# MotorSteuerung.net
KiCad netlist of a schematic drawn in EAGLE
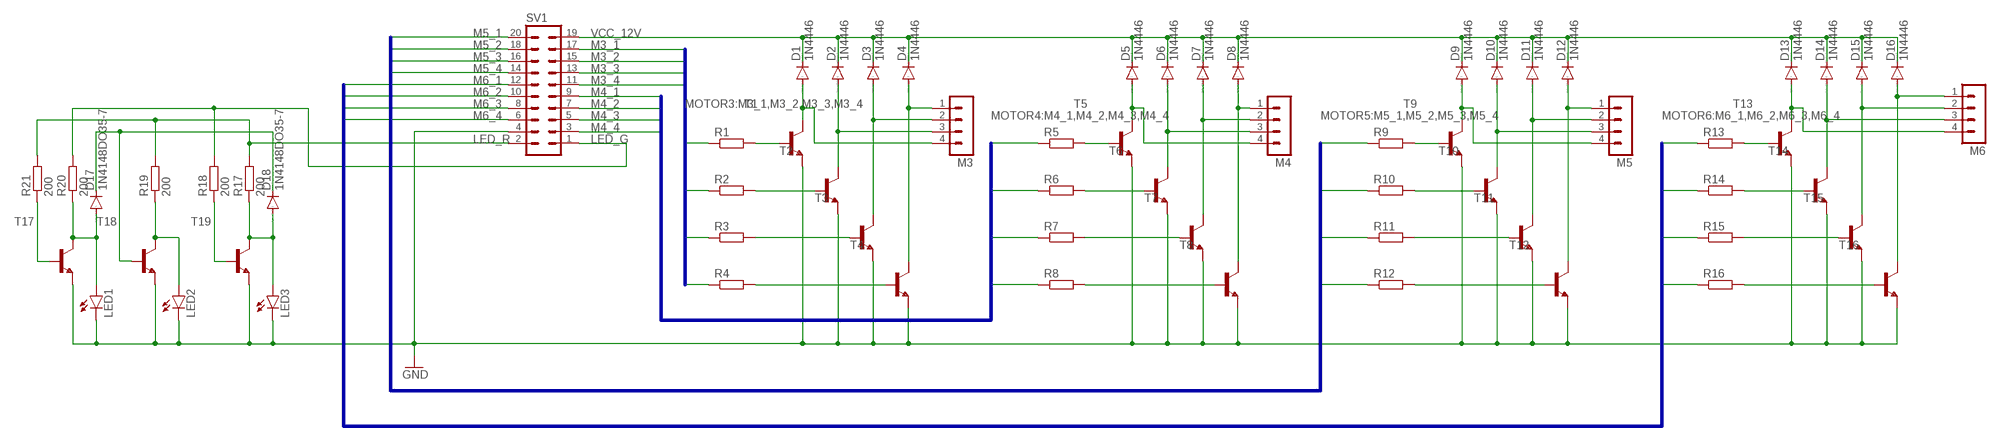
[diagram p0: schematic, sheet 1]

(export (version "E")
  (design (tool "Eeschema 10.0.6"))
  (components
    (comp (ref "D1")
      (value "1N4446")
      (footprint "eagle-import:DO35-10")
      (libsource (lib "eagle-import") (part "1N4446"))
    )
    (comp (ref "D2")
      (value "1N4446")
      (footprint "eagle-import:DO35-10")
      (libsource (lib "eagle-import") (part "1N4446"))
    )
    (comp (ref "D3")
      (value "1N4446")
      (footprint "eagle-import:DO35-10")
      (libsource (lib "eagle-import") (part "1N4446"))
    )
    (comp (ref "D4")
      (value "1N4446")
      (footprint "eagle-import:DO35-10")
      (libsource (lib "eagle-import") (part "1N4446"))
    )
    (comp (ref "D5")
      (value "1N4446")
      (footprint "eagle-import:DO35-10")
      (libsource (lib "eagle-import") (part "1N4446"))
    )
    (comp (ref "D6")
      (value "1N4446")
      (footprint "eagle-import:DO35-10")
      (libsource (lib "eagle-import") (part "1N4446"))
    )
    (comp (ref "D7")
      (value "1N4446")
      (footprint "eagle-import:DO35-10")
      (libsource (lib "eagle-import") (part "1N4446"))
    )
    (comp (ref "D8")
      (value "1N4446")
      (footprint "eagle-import:DO35-10")
      (libsource (lib "eagle-import") (part "1N4446"))
    )
    (comp (ref "D9")
      (value "1N4446")
      (footprint "eagle-import:DO35-10")
      (libsource (lib "eagle-import") (part "1N4446"))
    )
    (comp (ref "D10")
      (value "1N4446")
      (footprint "eagle-import:DO35-10")
      (libsource (lib "eagle-import") (part "1N4446"))
    )
    (comp (ref "D11")
      (value "1N4446")
      (footprint "eagle-import:DO35-10")
      (libsource (lib "eagle-import") (part "1N4446"))
    )
    (comp (ref "D12")
      (value "1N4446")
      (footprint "eagle-import:DO35-10")
      (libsource (lib "eagle-import") (part "1N4446"))
    )
    (comp (ref "D13")
      (value "1N4446")
      (footprint "eagle-import:DO35-10")
      (libsource (lib "eagle-import") (part "1N4446"))
    )
    (comp (ref "D14")
      (value "1N4446")
      (footprint "eagle-import:DO35-10")
      (libsource (lib "eagle-import") (part "1N4446"))
    )
    (comp (ref "D15")
      (value "1N4446")
      (footprint "eagle-import:DO35-10")
      (libsource (lib "eagle-import") (part "1N4446"))
    )
    (comp (ref "D16")
      (value "1N4446")
      (footprint "eagle-import:DO35-10")
      (libsource (lib "eagle-import") (part "1N4446"))
    )
    (comp (ref "D17")
      (value "1N4148DO35-7")
      (footprint "eagle-import:DO35-7")
      (libsource (lib "eagle-import") (part "1N4148DO35-7"))
    )
    (comp (ref "D18")
      (value "1N4148DO35-7")
      (footprint "eagle-import:DO35-7")
      (libsource (lib "eagle-import") (part "1N4148DO35-7"))
    )
    (comp (ref "LED1")
      (value "LED3MM")
      (footprint "eagle-import:LED3MM")
      (libsource (lib "eagle-import") (part "LED3MM"))
    )
    (comp (ref "LED2")
      (value "LED3MM")
      (footprint "eagle-import:LED3MM")
      (libsource (lib "eagle-import") (part "LED3MM"))
    )
    (comp (ref "LED3")
      (value "LED3MM")
      (footprint "eagle-import:LED3MM")
      (libsource (lib "eagle-import") (part "LED3MM"))
    )
    (comp (ref "M3")
      (value "MA04-1")
      (footprint "eagle-import:MA04-1")
      (libsource (lib "eagle-import") (part "MA04-1"))
    )
    (comp (ref "M4")
      (value "MA04-1")
      (footprint "eagle-import:MA04-1")
      (libsource (lib "eagle-import") (part "MA04-1"))
    )
    (comp (ref "M5")
      (value "MA04-1")
      (footprint "eagle-import:MA04-1")
      (libsource (lib "eagle-import") (part "MA04-1"))
    )
    (comp (ref "M6")
      (value "MA04-1")
      (footprint "eagle-import:MA04-1")
      (libsource (lib "eagle-import") (part "MA04-1"))
    )
    (comp (ref "R1")
      (value "R-EU_0207/10")
      (footprint "eagle-import:0207_10")
      (libsource (lib "eagle-import") (part "R-EU_0207/10"))
    )
    (comp (ref "R2")
      (value "R-EU_0207/10")
      (footprint "eagle-import:0207_10")
      (libsource (lib "eagle-import") (part "R-EU_0207/10"))
    )
    (comp (ref "R3")
      (value "R-EU_0207/10")
      (footprint "eagle-import:0207_10")
      (libsource (lib "eagle-import") (part "R-EU_0207/10"))
    )
    (comp (ref "R4")
      (value "R-EU_0207/10")
      (footprint "eagle-import:0207_10")
      (libsource (lib "eagle-import") (part "R-EU_0207/10"))
    )
    (comp (ref "R5")
      (value "R-EU_0207/10")
      (footprint "eagle-import:0207_10")
      (libsource (lib "eagle-import") (part "R-EU_0207/10"))
    )
    (comp (ref "R6")
      (value "R-EU_0207/10")
      (footprint "eagle-import:0207_10")
      (libsource (lib "eagle-import") (part "R-EU_0207/10"))
    )
    (comp (ref "R7")
      (value "R-EU_0207/10")
      (footprint "eagle-import:0207_10")
      (libsource (lib "eagle-import") (part "R-EU_0207/10"))
    )
    (comp (ref "R8")
      (value "R-EU_0207/10")
      (footprint "eagle-import:0207_10")
      (libsource (lib "eagle-import") (part "R-EU_0207/10"))
    )
    (comp (ref "R9")
      (value "R-EU_0207/10")
      (footprint "eagle-import:0207_10")
      (libsource (lib "eagle-import") (part "R-EU_0207/10"))
    )
    (comp (ref "R10")
      (value "R-EU_0207/10")
      (footprint "eagle-import:0207_10")
      (libsource (lib "eagle-import") (part "R-EU_0207/10"))
    )
    (comp (ref "R11")
      (value "R-EU_0207/10")
      (footprint "eagle-import:0207_10")
      (libsource (lib "eagle-import") (part "R-EU_0207/10"))
    )
    (comp (ref "R12")
      (value "R-EU_0207/10")
      (footprint "eagle-import:0207_10")
      (libsource (lib "eagle-import") (part "R-EU_0207/10"))
    )
    (comp (ref "R13")
      (value "R-EU_0207/10")
      (footprint "eagle-import:0207_10")
      (libsource (lib "eagle-import") (part "R-EU_0207/10"))
    )
    (comp (ref "R14")
      (value "R-EU_0207/10")
      (footprint "eagle-import:0207_10")
      (libsource (lib "eagle-import") (part "R-EU_0207/10"))
    )
    (comp (ref "R15")
      (value "R-EU_0207/10")
      (footprint "eagle-import:0207_10")
      (libsource (lib "eagle-import") (part "R-EU_0207/10"))
    )
    (comp (ref "R16")
      (value "R-EU_0207/10")
      (footprint "eagle-import:0207_10")
      (libsource (lib "eagle-import") (part "R-EU_0207/10"))
    )
    (comp (ref "R17")
      (value "200")
      (footprint "eagle-import:0207_10")
      (libsource (lib "eagle-import") (part "R-EU_0207/10"))
    )
    (comp (ref "R18")
      (value "200")
      (footprint "eagle-import:0207_10")
      (libsource (lib "eagle-import") (part "R-EU_0207/10"))
    )
    (comp (ref "R19")
      (value "200")
      (footprint "eagle-import:0207_10")
      (libsource (lib "eagle-import") (part "R-EU_0207/10"))
    )
    (comp (ref "R20")
      (value "200")
      (footprint "eagle-import:0207_10")
      (libsource (lib "eagle-import") (part "R-EU_0207/10"))
    )
    (comp (ref "R21")
      (value "200")
      (footprint "eagle-import:0207_10")
      (libsource (lib "eagle-import") (part "R-EU_0207/10"))
    )
    (comp (ref "SV1")
      (value "MA10-2")
      (footprint "eagle-import:MA10-2")
      (libsource (lib "eagle-import") (part "MA10-2"))
    )
    (comp (ref "T1")
      (value "-NPN-TO126V")
      (footprint "eagle-import:TO126V")
      (libsource (lib "eagle-import") (part "-NPN-TO126V"))
    )
    (comp (ref "T2")
      (value "-NPN-TO126V")
      (footprint "eagle-import:TO126V")
      (libsource (lib "eagle-import") (part "-NPN-TO126V"))
    )
    (comp (ref "T3")
      (value "-NPN-TO126V")
      (footprint "eagle-import:TO126V")
      (libsource (lib "eagle-import") (part "-NPN-TO126V"))
    )
    (comp (ref "T4")
      (value "-NPN-TO126V")
      (footprint "eagle-import:TO126V")
      (libsource (lib "eagle-import") (part "-NPN-TO126V"))
    )
    (comp (ref "T5")
      (value "-NPN-TO126V")
      (footprint "eagle-import:TO126V")
      (libsource (lib "eagle-import") (part "-NPN-TO126V"))
    )
    (comp (ref "T6")
      (value "-NPN-TO126V")
      (footprint "eagle-import:TO126V")
      (libsource (lib "eagle-import") (part "-NPN-TO126V"))
    )
    (comp (ref "T7")
      (value "-NPN-TO126V")
      (footprint "eagle-import:TO126V")
      (libsource (lib "eagle-import") (part "-NPN-TO126V"))
    )
    (comp (ref "T8")
      (value "-NPN-TO126V")
      (footprint "eagle-import:TO126V")
      (libsource (lib "eagle-import") (part "-NPN-TO126V"))
    )
    (comp (ref "T9")
      (value "-NPN-TO126V")
      (footprint "eagle-import:TO126V")
      (libsource (lib "eagle-import") (part "-NPN-TO126V"))
    )
    (comp (ref "T10")
      (value "-NPN-TO126V")
      (footprint "eagle-import:TO126V")
      (libsource (lib "eagle-import") (part "-NPN-TO126V"))
    )
    (comp (ref "T11")
      (value "-NPN-TO126V")
      (footprint "eagle-import:TO126V")
      (libsource (lib "eagle-import") (part "-NPN-TO126V"))
    )
    (comp (ref "T12")
      (value "-NPN-TO126V")
      (footprint "eagle-import:TO126V")
      (libsource (lib "eagle-import") (part "-NPN-TO126V"))
    )
    (comp (ref "T13")
      (value "-NPN-TO126V")
      (footprint "eagle-import:TO126V")
      (libsource (lib "eagle-import") (part "-NPN-TO126V"))
    )
    (comp (ref "T14")
      (value "-NPN-TO126V")
      (footprint "eagle-import:TO126V")
      (libsource (lib "eagle-import") (part "-NPN-TO126V"))
    )
    (comp (ref "T15")
      (value "-NPN-TO126V")
      (footprint "eagle-import:TO126V")
      (libsource (lib "eagle-import") (part "-NPN-TO126V"))
    )
    (comp (ref "T16")
      (value "-NPN-TO126V")
      (footprint "eagle-import:TO126V")
      (libsource (lib "eagle-import") (part "-NPN-TO126V"))
    )
    (comp (ref "T17")
      (value "-NPN-TO92")
      (footprint "eagle-import:TO92")
      (libsource (lib "eagle-import") (part "-NPN-TO92"))
    )
    (comp (ref "T18")
      (value "-NPN-TO92")
      (footprint "eagle-import:TO92")
      (libsource (lib "eagle-import") (part "-NPN-TO92"))
    )
    (comp (ref "T19")
      (value "-NPN-TO92")
      (footprint "eagle-import:TO92")
      (libsource (lib "eagle-import") (part "-NPN-TO92"))
    )
  )
  (nets
    (net (code "5") (name "/LED_G") (class "Default")
      (node (ref "R18") (pin "2") (pinfunction "2_2") (pintype "passive"))
      (node (ref "R20") (pin "2") (pinfunction "2_2") (pintype "passive"))
      (node (ref "SV1") (pin "1") (pinfunction "1_1") (pintype "passive"))
    )
    (net (code "6") (name "/LED_R") (class "Default")
      (node (ref "R17") (pin "2") (pinfunction "2_2") (pintype "passive"))
      (node (ref "R19") (pin "2") (pinfunction "2_2") (pintype "passive"))
      (node (ref "R21") (pin "2") (pinfunction "2_2") (pintype "passive"))
      (node (ref "SV1") (pin "2") (pinfunction "2_2") (pintype "passive"))
    )
    (net (code "7") (name "/M3_1") (class "Default")
      (node (ref "R1") (pin "1") (pinfunction "1_1") (pintype "passive"))
      (node (ref "SV1") (pin "17") (pinfunction "17_17") (pintype "passive"))
    )
    (net (code "8") (name "/M3_2") (class "Default")
      (node (ref "R2") (pin "1") (pinfunction "1_1") (pintype "passive"))
      (node (ref "SV1") (pin "15") (pinfunction "15_15") (pintype "passive"))
    )
    (net (code "9") (name "/M3_3") (class "Default")
      (node (ref "R3") (pin "1") (pinfunction "1_1") (pintype "passive"))
      (node (ref "SV1") (pin "13") (pinfunction "13_13") (pintype "passive"))
    )
    (net (code "10") (name "/M3_4") (class "Default")
      (node (ref "R4") (pin "1") (pinfunction "1_1") (pintype "passive"))
      (node (ref "SV1") (pin "11") (pinfunction "11_11") (pintype "passive"))
    )
    (net (code "11") (name "/M4_1") (class "Default")
      (node (ref "R5") (pin "1") (pinfunction "1_1") (pintype "passive"))
      (node (ref "SV1") (pin "9") (pinfunction "9_9") (pintype "passive"))
    )
    (net (code "12") (name "/M4_2") (class "Default")
      (node (ref "R6") (pin "1") (pinfunction "1_1") (pintype "passive"))
      (node (ref "SV1") (pin "7") (pinfunction "7_7") (pintype "passive"))
    )
    (net (code "13") (name "/M4_3") (class "Default")
      (node (ref "R7") (pin "1") (pinfunction "1_1") (pintype "passive"))
      (node (ref "SV1") (pin "5") (pinfunction "5_5") (pintype "passive"))
    )
    (net (code "14") (name "/M4_4") (class "Default")
      (node (ref "R8") (pin "1") (pinfunction "1_1") (pintype "passive"))
      (node (ref "SV1") (pin "3") (pinfunction "3_3") (pintype "passive"))
    )
    (net (code "15") (name "/M5_1") (class "Default")
      (node (ref "R9") (pin "1") (pinfunction "1_1") (pintype "passive"))
      (node (ref "SV1") (pin "20") (pinfunction "20_20") (pintype "passive"))
    )
    (net (code "16") (name "/M5_2") (class "Default")
      (node (ref "R10") (pin "1") (pinfunction "1_1") (pintype "passive"))
      (node (ref "SV1") (pin "18") (pinfunction "18_18") (pintype "passive"))
    )
    (net (code "17") (name "/M5_3") (class "Default")
      (node (ref "R11") (pin "1") (pinfunction "1_1") (pintype "passive"))
      (node (ref "SV1") (pin "16") (pinfunction "16_16") (pintype "passive"))
    )
    (net (code "18") (name "/M5_4") (class "Default")
      (node (ref "R12") (pin "1") (pinfunction "1_1") (pintype "passive"))
      (node (ref "SV1") (pin "14") (pinfunction "14_14") (pintype "passive"))
    )
    (net (code "19") (name "/M6_1") (class "Default")
      (node (ref "R13") (pin "1") (pinfunction "1_1") (pintype "passive"))
      (node (ref "SV1") (pin "12") (pinfunction "12_12") (pintype "passive"))
    )
    (net (code "20") (name "/M6_2") (class "Default")
      (node (ref "R14") (pin "1") (pinfunction "1_1") (pintype "passive"))
      (node (ref "SV1") (pin "10") (pinfunction "10_10") (pintype "passive"))
    )
    (net (code "21") (name "/M6_3") (class "Default")
      (node (ref "R15") (pin "1") (pinfunction "1_1") (pintype "passive"))
      (node (ref "SV1") (pin "8") (pinfunction "8_8") (pintype "passive"))
    )
    (net (code "22") (name "/M6_4") (class "Default")
      (node (ref "R16") (pin "1") (pinfunction "1_1") (pintype "passive"))
      (node (ref "SV1") (pin "6") (pinfunction "6_6") (pintype "passive"))
    )
    (net (code "23") (name "/VCC_12V") (class "Default")
      (node (ref "D1") (pin "C") (pinfunction "C_C") (pintype "passive"))
      (node (ref "D10") (pin "C") (pinfunction "C_C") (pintype "passive"))
      (node (ref "D11") (pin "C") (pinfunction "C_C") (pintype "passive"))
      (node (ref "D12") (pin "C") (pinfunction "C_C") (pintype "passive"))
      (node (ref "D13") (pin "C") (pinfunction "C_C") (pintype "passive"))
      (node (ref "D14") (pin "C") (pinfunction "C_C") (pintype "passive"))
      (node (ref "D15") (pin "C") (pinfunction "C_C") (pintype "passive"))
      (node (ref "D16") (pin "C") (pinfunction "C_C") (pintype "passive"))
      (node (ref "D2") (pin "C") (pinfunction "C_C") (pintype "passive"))
      (node (ref "D3") (pin "C") (pinfunction "C_C") (pintype "passive"))
      (node (ref "D4") (pin "C") (pinfunction "C_C") (pintype "passive"))
      (node (ref "D5") (pin "C") (pinfunction "C_C") (pintype "passive"))
      (node (ref "D6") (pin "C") (pinfunction "C_C") (pintype "passive"))
      (node (ref "D7") (pin "C") (pinfunction "C_C") (pintype "passive"))
      (node (ref "D8") (pin "C") (pinfunction "C_C") (pintype "passive"))
      (node (ref "D9") (pin "C") (pinfunction "C_C") (pintype "passive"))
      (node (ref "SV1") (pin "19") (pinfunction "19_19") (pintype "passive"))
    )
    (net (code "28") (name "GND") (class "Default")
      (node (ref "LED1") (pin "K") (pinfunction "C_K") (pintype "passive"))
      (node (ref "LED2") (pin "K") (pinfunction "C_K") (pintype "passive"))
      (node (ref "LED3") (pin "K") (pinfunction "C_K") (pintype "passive"))
      (node (ref "SV1") (pin "4") (pinfunction "4_4") (pintype "passive"))
      (node (ref "T1") (pin "1") (pinfunction "E_1") (pintype "passive"))
      (node (ref "T10") (pin "1") (pinfunction "E_1") (pintype "passive"))
      (node (ref "T11") (pin "1") (pinfunction "E_1") (pintype "passive"))
      (node (ref "T12") (pin "1") (pinfunction "E_1") (pintype "passive"))
      (node (ref "T13") (pin "1") (pinfunction "E_1") (pintype "passive"))
      (node (ref "T14") (pin "1") (pinfunction "E_1") (pintype "passive"))
      (node (ref "T15") (pin "1") (pinfunction "E_1") (pintype "passive"))
      (node (ref "T16") (pin "1") (pinfunction "E_1") (pintype "passive"))
      (node (ref "T17") (pin "1") (pinfunction "E_1") (pintype "passive"))
      (node (ref "T18") (pin "1") (pinfunction "E_1") (pintype "passive"))
      (node (ref "T19") (pin "1") (pinfunction "E_1") (pintype "passive"))
      (node (ref "T2") (pin "1") (pinfunction "E_1") (pintype "passive"))
      (node (ref "T3") (pin "1") (pinfunction "E_1") (pintype "passive"))
      (node (ref "T4") (pin "1") (pinfunction "E_1") (pintype "passive"))
      (node (ref "T5") (pin "1") (pinfunction "E_1") (pintype "passive"))
      (node (ref "T6") (pin "1") (pinfunction "E_1") (pintype "passive"))
      (node (ref "T7") (pin "1") (pinfunction "E_1") (pintype "passive"))
      (node (ref "T8") (pin "1") (pinfunction "E_1") (pintype "passive"))
      (node (ref "T9") (pin "1") (pinfunction "E_1") (pintype "passive"))
    )
    (net (code "29") (name "Net-(T1-B)") (class "Default")
      (node (ref "R1") (pin "2") (pinfunction "2_2") (pintype "passive"))
      (node (ref "T1") (pin "3") (pinfunction "B_3") (pintype "passive"))
    )
    (net (code "30") (name "Net-(T1-C)") (class "Default")
      (node (ref "D1") (pin "A") (pinfunction "A_A") (pintype "passive"))
      (node (ref "M3") (pin "4") (pinfunction "4_4") (pintype "passive"))
      (node (ref "T1") (pin "2") (pinfunction "C_2") (pintype "passive"))
    )
    (net (code "31") (name "Net-(T2-B)") (class "Default")
      (node (ref "R2") (pin "2") (pinfunction "2_2") (pintype "passive"))
      (node (ref "T2") (pin "3") (pinfunction "B_3") (pintype "passive"))
    )
    (net (code "32") (name "Net-(T2-C)") (class "Default")
      (node (ref "D2") (pin "A") (pinfunction "A_A") (pintype "passive"))
      (node (ref "M3") (pin "3") (pinfunction "3_3") (pintype "passive"))
      (node (ref "T2") (pin "2") (pinfunction "C_2") (pintype "passive"))
    )
    (net (code "33") (name "Net-(T3-B)") (class "Default")
      (node (ref "R3") (pin "2") (pinfunction "2_2") (pintype "passive"))
      (node (ref "T3") (pin "3") (pinfunction "B_3") (pintype "passive"))
    )
    (net (code "34") (name "Net-(T3-C)") (class "Default")
      (node (ref "D3") (pin "A") (pinfunction "A_A") (pintype "passive"))
      (node (ref "M3") (pin "2") (pinfunction "2_2") (pintype "passive"))
      (node (ref "T3") (pin "2") (pinfunction "C_2") (pintype "passive"))
    )
    (net (code "35") (name "Net-(T4-B)") (class "Default")
      (node (ref "R4") (pin "2") (pinfunction "2_2") (pintype "passive"))
      (node (ref "T4") (pin "3") (pinfunction "B_3") (pintype "passive"))
    )
    (net (code "36") (name "Net-(T4-C)") (class "Default")
      (node (ref "D4") (pin "A") (pinfunction "A_A") (pintype "passive"))
      (node (ref "M3") (pin "1") (pinfunction "1_1") (pintype "passive"))
      (node (ref "T4") (pin "2") (pinfunction "C_2") (pintype "passive"))
    )
    (net (code "37") (name "Net-(T5-B)") (class "Default")
      (node (ref "R5") (pin "2") (pinfunction "2_2") (pintype "passive"))
      (node (ref "T5") (pin "3") (pinfunction "B_3") (pintype "passive"))
    )
    (net (code "38") (name "Net-(T5-C)") (class "Default")
      (node (ref "D5") (pin "A") (pinfunction "A_A") (pintype "passive"))
      (node (ref "M4") (pin "4") (pinfunction "4_4") (pintype "passive"))
      (node (ref "T5") (pin "2") (pinfunction "C_2") (pintype "passive"))
    )
    (net (code "39") (name "Net-(T6-B)") (class "Default")
      (node (ref "R6") (pin "2") (pinfunction "2_2") (pintype "passive"))
      (node (ref "T6") (pin "3") (pinfunction "B_3") (pintype "passive"))
    )
    (net (code "40") (name "Net-(T6-C)") (class "Default")
      (node (ref "D6") (pin "A") (pinfunction "A_A") (pintype "passive"))
      (node (ref "M4") (pin "3") (pinfunction "3_3") (pintype "passive"))
      (node (ref "T6") (pin "2") (pinfunction "C_2") (pintype "passive"))
    )
    (net (code "41") (name "Net-(T7-B)") (class "Default")
      (node (ref "R7") (pin "2") (pinfunction "2_2") (pintype "passive"))
      (node (ref "T7") (pin "3") (pinfunction "B_3") (pintype "passive"))
    )
    (net (code "42") (name "Net-(T7-C)") (class "Default")
      (node (ref "D7") (pin "A") (pinfunction "A_A") (pintype "passive"))
      (node (ref "M4") (pin "2") (pinfunction "2_2") (pintype "passive"))
      (node (ref "T7") (pin "2") (pinfunction "C_2") (pintype "passive"))
    )
    (net (code "43") (name "Net-(T8-B)") (class "Default")
      (node (ref "R8") (pin "2") (pinfunction "2_2") (pintype "passive"))
      (node (ref "T8") (pin "3") (pinfunction "B_3") (pintype "passive"))
    )
    (net (code "44") (name "Net-(T8-C)") (class "Default")
      (node (ref "D8") (pin "A") (pinfunction "A_A") (pintype "passive"))
      (node (ref "M4") (pin "1") (pinfunction "1_1") (pintype "passive"))
      (node (ref "T8") (pin "2") (pinfunction "C_2") (pintype "passive"))
    )
    (net (code "45") (name "Net-(T9-B)") (class "Default")
      (node (ref "R9") (pin "2") (pinfunction "2_2") (pintype "passive"))
      (node (ref "T9") (pin "3") (pinfunction "B_3") (pintype "passive"))
    )
    (net (code "46") (name "Net-(T9-C)") (class "Default")
      (node (ref "D9") (pin "A") (pinfunction "A_A") (pintype "passive"))
      (node (ref "M5") (pin "4") (pinfunction "4_4") (pintype "passive"))
      (node (ref "T9") (pin "2") (pinfunction "C_2") (pintype "passive"))
    )
    (net (code "47") (name "Net-(T10-B)") (class "Default")
      (node (ref "R10") (pin "2") (pinfunction "2_2") (pintype "passive"))
      (node (ref "T10") (pin "3") (pinfunction "B_3") (pintype "passive"))
    )
    (net (code "48") (name "Net-(T10-C)") (class "Default")
      (node (ref "D10") (pin "A") (pinfunction "A_A") (pintype "passive"))
      (node (ref "M5") (pin "3") (pinfunction "3_3") (pintype "passive"))
      (node (ref "T10") (pin "2") (pinfunction "C_2") (pintype "passive"))
    )
    (net (code "49") (name "Net-(T11-B)") (class "Default")
      (node (ref "R11") (pin "2") (pinfunction "2_2") (pintype "passive"))
      (node (ref "T11") (pin "3") (pinfunction "B_3") (pintype "passive"))
    )
    (net (code "50") (name "Net-(T11-C)") (class "Default")
      (node (ref "D11") (pin "A") (pinfunction "A_A") (pintype "passive"))
      (node (ref "M5") (pin "2") (pinfunction "2_2") (pintype "passive"))
      (node (ref "T11") (pin "2") (pinfunction "C_2") (pintype "passive"))
    )
    (net (code "51") (name "Net-(T12-B)") (class "Default")
      (node (ref "R12") (pin "2") (pinfunction "2_2") (pintype "passive"))
      (node (ref "T12") (pin "3") (pinfunction "B_3") (pintype "passive"))
    )
    (net (code "52") (name "Net-(T12-C)") (class "Default")
      (node (ref "D12") (pin "A") (pinfunction "A_A") (pintype "passive"))
      (node (ref "M5") (pin "1") (pinfunction "1_1") (pintype "passive"))
      (node (ref "T12") (pin "2") (pinfunction "C_2") (pintype "passive"))
    )
    (net (code "53") (name "Net-(T13-B)") (class "Default")
      (node (ref "R13") (pin "2") (pinfunction "2_2") (pintype "passive"))
      (node (ref "T13") (pin "3") (pinfunction "B_3") (pintype "passive"))
    )
    (net (code "54") (name "Net-(T13-C)") (class "Default")
      (node (ref "D13") (pin "A") (pinfunction "A_A") (pintype "passive"))
      (node (ref "M6") (pin "4") (pinfunction "4_4") (pintype "passive"))
      (node (ref "T13") (pin "2") (pinfunction "C_2") (pintype "passive"))
    )
    (net (code "55") (name "Net-(T14-B)") (class "Default")
      (node (ref "R14") (pin "2") (pinfunction "2_2") (pintype "passive"))
      (node (ref "T14") (pin "3") (pinfunction "B_3") (pintype "passive"))
    )
    (net (code "56") (name "Net-(T14-C)") (class "Default")
      (node (ref "D14") (pin "A") (pinfunction "A_A") (pintype "passive"))
      (node (ref "M6") (pin "3") (pinfunction "3_3") (pintype "passive"))
      (node (ref "T14") (pin "2") (pinfunction "C_2") (pintype "passive"))
    )
    (net (code "57") (name "Net-(T15-B)") (class "Default")
      (node (ref "R15") (pin "2") (pinfunction "2_2") (pintype "passive"))
      (node (ref "T15") (pin "3") (pinfunction "B_3") (pintype "passive"))
    )
    (net (code "58") (name "Net-(T15-C)") (class "Default")
      (node (ref "D15") (pin "A") (pinfunction "A_A") (pintype "passive"))
      (node (ref "M6") (pin "2") (pinfunction "2_2") (pintype "passive"))
      (node (ref "T15") (pin "2") (pinfunction "C_2") (pintype "passive"))
    )
    (net (code "59") (name "Net-(T16-B)") (class "Default")
      (node (ref "R16") (pin "2") (pinfunction "2_2") (pintype "passive"))
      (node (ref "T16") (pin "3") (pinfunction "B_3") (pintype "passive"))
    )
    (net (code "60") (name "Net-(T16-C)") (class "Default")
      (node (ref "D16") (pin "A") (pinfunction "A_A") (pintype "passive"))
      (node (ref "M6") (pin "1") (pinfunction "1_1") (pintype "passive"))
      (node (ref "T16") (pin "2") (pinfunction "C_2") (pintype "passive"))
    )
    (net (code "61") (name "Net-(T17-B)") (class "Default")
      (node (ref "R21") (pin "1") (pinfunction "1_1") (pintype "passive"))
      (node (ref "T17") (pin "2") (pinfunction "B_2") (pintype "passive"))
    )
    (net (code "62") (name "Net-(T17-C)") (class "Default")
      (node (ref "D17") (pin "A") (pinfunction "A_A") (pintype "passive"))
      (node (ref "LED1") (pin "A") (pinfunction "A_A") (pintype "passive"))
      (node (ref "R20") (pin "1") (pinfunction "1_1") (pintype "passive"))
      (node (ref "T17") (pin "3") (pinfunction "C_3") (pintype "passive"))
    )
    (net (code "63") (name "Net-(T18-B)") (class "Default")
      (node (ref "D17") (pin "C") (pinfunction "C_C") (pintype "passive"))
      (node (ref "D18") (pin "C") (pinfunction "C_C") (pintype "passive"))
      (node (ref "T18") (pin "2") (pinfunction "B_2") (pintype "passive"))
    )
    (net (code "64") (name "Net-(T18-C)") (class "Default")
      (node (ref "LED2") (pin "A") (pinfunction "A_A") (pintype "passive"))
      (node (ref "R19") (pin "1") (pinfunction "1_1") (pintype "passive"))
      (node (ref "T18") (pin "3") (pinfunction "C_3") (pintype "passive"))
    )
    (net (code "65") (name "Net-(T19-B)") (class "Default")
      (node (ref "R18") (pin "1") (pinfunction "1_1") (pintype "passive"))
      (node (ref "T19") (pin "2") (pinfunction "B_2") (pintype "passive"))
    )
    (net (code "66") (name "Net-(T19-C)") (class "Default")
      (node (ref "D18") (pin "A") (pinfunction "A_A") (pintype "passive"))
      (node (ref "LED3") (pin "A") (pinfunction "A_A") (pintype "passive"))
      (node (ref "R17") (pin "1") (pinfunction "1_1") (pintype "passive"))
      (node (ref "T19") (pin "3") (pinfunction "C_3") (pintype "passive"))
    )
  )
)
